# port.net
KiCad netlist of a schematic drawn in Altium Designer
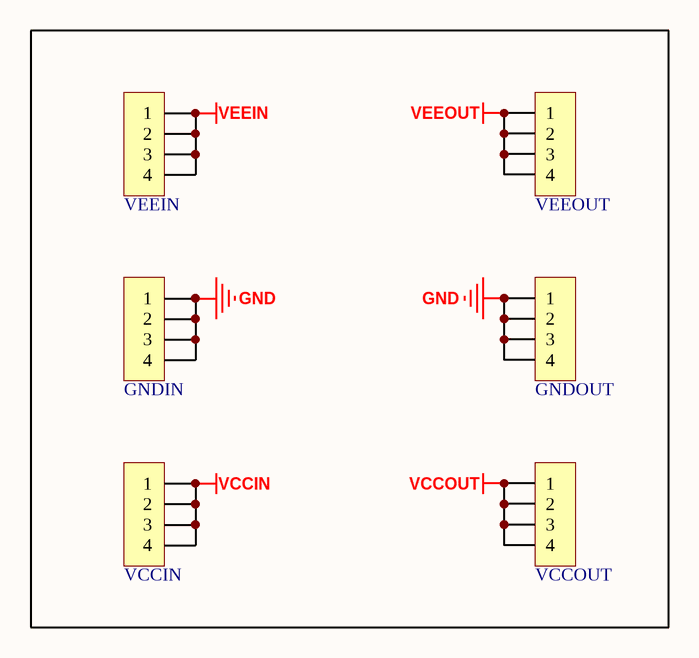
[diagram p0: port.SchDoc]

(export (version "E")
  (design (tool "Eeschema 10.0.6"))
  (components
    (comp (ref "GNDIN")
      (value "HDR-1X4")
      (footprint "HDR2.54-LI-4P")
      (description "4P接插件")
      (fields (field (name "版权归属") "源创客"))
      (libsource (lib "IL") (part "Header 4"))
    )
    (comp (ref "GNDOUT")
      (value "HDR-1X4")
      (footprint "HDR2.54-LI-4P")
      (description "4P接插件")
      (fields (field (name "版权归属") "源创客"))
      (libsource (lib "") (part "Header 4_1"))
    )
    (comp (ref "VCCIN")
      (value "HDR-1X4")
      (footprint "HDR2.54-LI-4P")
      (description "4P接插件")
      (fields (field (name "版权归属") "源创客"))
      (libsource (lib "IL") (part "Header 4"))
    )
    (comp (ref "VCCOUT")
      (value "HDR-1X4")
      (footprint "HDR2.54-LI-4P")
      (description "4P接插件")
      (fields (field (name "版权归属") "源创客"))
      (libsource (lib "") (part "Header 4_1"))
    )
    (comp (ref "VEEIN")
      (value "HDR-1X4")
      (footprint "HDR2.54-LI-4P")
      (description "4P接插件")
      (fields (field (name "版权归属") "源创客"))
      (libsource (lib "IL") (part "Header 4"))
    )
    (comp (ref "VEEOUT")
      (value "HDR-1X4")
      (footprint "HDR2.54-LI-4P")
      (description "4P接插件")
      (fields (field (name "版权归属") "源创客"))
      (libsource (lib "") (part "Header 4_1"))
    )
  )
  (nets
    (net (code "1") (name "GND") (class "Default")
      (node (ref "GNDIN") (pin "1") (pinfunction "1_1") (pintype "passive"))
      (node (ref "GNDIN") (pin "2") (pinfunction "2_2") (pintype "passive"))
      (node (ref "GNDIN") (pin "3") (pinfunction "3_3") (pintype "passive"))
      (node (ref "GNDIN") (pin "4") (pinfunction "4_4") (pintype "passive"))
      (node (ref "GNDOUT") (pin "1") (pinfunction "1_1") (pintype "passive"))
      (node (ref "GNDOUT") (pin "2") (pinfunction "2_2") (pintype "passive"))
      (node (ref "GNDOUT") (pin "3") (pinfunction "3_3") (pintype "passive"))
      (node (ref "GNDOUT") (pin "4") (pinfunction "4_4") (pintype "passive"))
    )
    (net (code "2") (name "VCCIN") (class "Default")
      (node (ref "VCCIN") (pin "1") (pinfunction "1_1") (pintype "passive"))
      (node (ref "VCCIN") (pin "2") (pinfunction "2_2") (pintype "passive"))
      (node (ref "VCCIN") (pin "3") (pinfunction "3_3") (pintype "passive"))
      (node (ref "VCCIN") (pin "4") (pinfunction "4_4") (pintype "passive"))
    )
    (net (code "3") (name "VCCOUT") (class "Default")
      (node (ref "VCCOUT") (pin "1") (pinfunction "1_1") (pintype "passive"))
      (node (ref "VCCOUT") (pin "2") (pinfunction "2_2") (pintype "passive"))
      (node (ref "VCCOUT") (pin "3") (pinfunction "3_3") (pintype "passive"))
      (node (ref "VCCOUT") (pin "4") (pinfunction "4_4") (pintype "passive"))
    )
    (net (code "4") (name "VEEIN") (class "Default")
      (node (ref "VEEIN") (pin "1") (pinfunction "1_1") (pintype "passive"))
      (node (ref "VEEIN") (pin "2") (pinfunction "2_2") (pintype "passive"))
      (node (ref "VEEIN") (pin "3") (pinfunction "3_3") (pintype "passive"))
      (node (ref "VEEIN") (pin "4") (pinfunction "4_4") (pintype "passive"))
    )
    (net (code "5") (name "VEEOUT") (class "Default")
      (node (ref "VEEOUT") (pin "1") (pinfunction "1_1") (pintype "passive"))
      (node (ref "VEEOUT") (pin "2") (pinfunction "2_2") (pintype "passive"))
      (node (ref "VEEOUT") (pin "3") (pinfunction "3_3") (pintype "passive"))
      (node (ref "VEEOUT") (pin "4") (pinfunction "4_4") (pintype "passive"))
    )
  )
)
